# TWELITE_meas_2.net
KiCad netlist of a schematic drawn in EAGLE
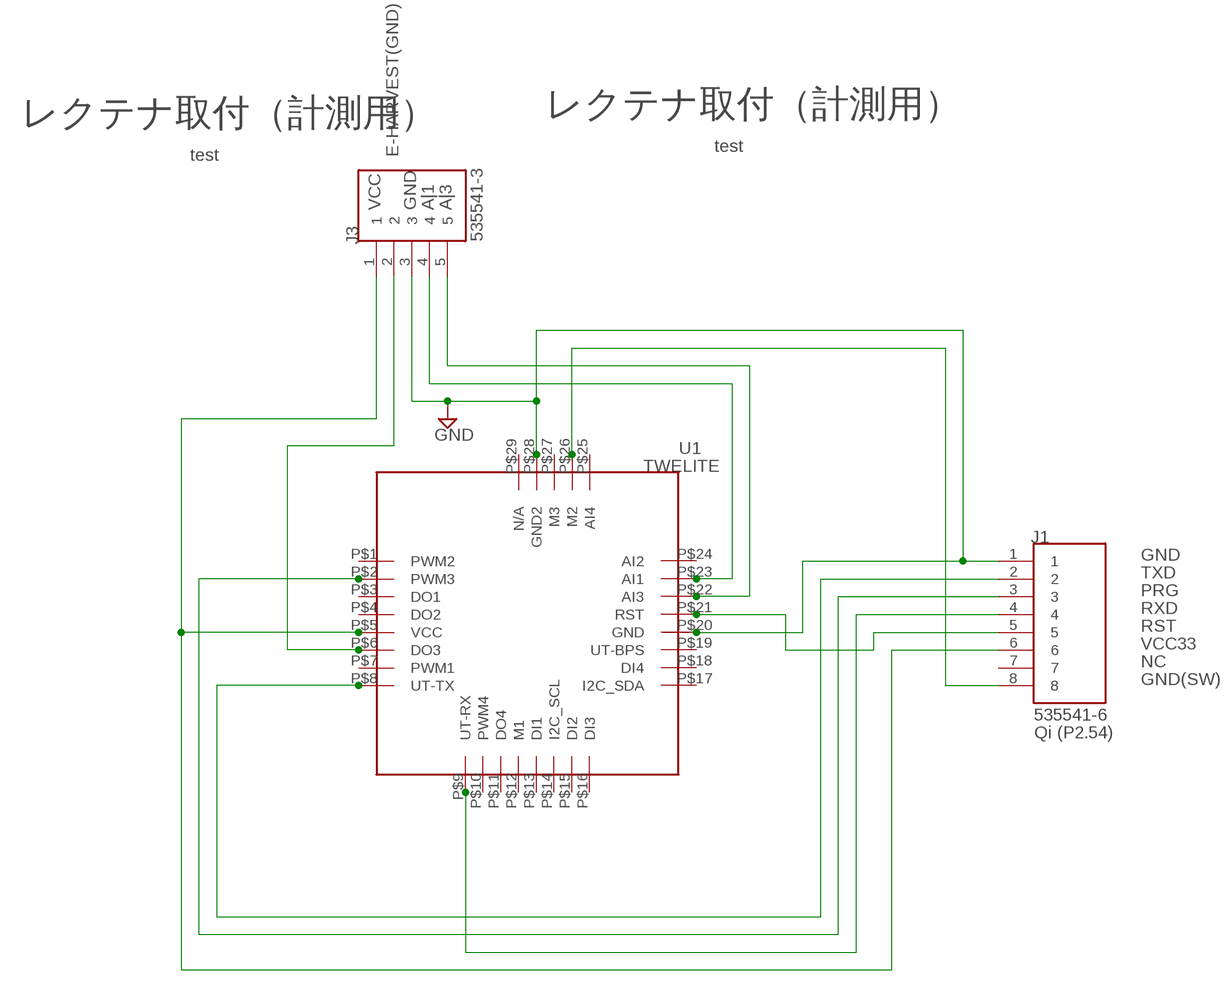
[diagram p0: schematic, sheet 1]

(export (version "E")
  (design (tool "Eeschema 10.0.6"))
  (components
    (comp (ref "J1")
      (value "535541-6")
      (footprint "eagle-import:TE_535541-6")
      (fields (field (name "MF") "TE Connectivity"))
      (libsource (lib "eagle-import") (part "535541-6"))
    )
    (comp (ref "J3")
      (value "535541-3")
      (footprint "eagle-import:TE_535541-3")
      (libsource (lib "eagle-import") (part "535541-3"))
    )
    (comp (ref "U1")
      (value "LITE_1")
      (footprint "eagle-import:LITE_1")
      (libsource (lib "eagle-import") (part "LITE_1"))
    )
  )
  (nets
    (net (code "1") (name "GND") (class "Default")
      (node (ref "J1") (pin "1") (pinfunction "1_1") (pintype "passive"))
      (node (ref "J3") (pin "3") (pinfunction "3_3") (pintype "passive"))
      (node (ref "U1") (pin "P$20") (pinfunction "GND_P$20") (pintype "bidirectional"))
      (node (ref "U1") (pin "P$28") (pinfunction "GND2_P$28") (pintype "bidirectional"))
    )
    (net (code "2") (name "Net-(U1-AI1)") (class "Default")
      (node (ref "J3") (pin "4") (pinfunction "4_4") (pintype "passive"))
      (node (ref "U1") (pin "P$23") (pinfunction "AI1_P$23") (pintype "bidirectional"))
    )
    (net (code "3") (name "Net-(U1-AI3)") (class "Default")
      (node (ref "J3") (pin "5") (pinfunction "5_5") (pintype "passive"))
      (node (ref "U1") (pin "P$22") (pinfunction "AI3_P$22") (pintype "bidirectional"))
    )
    (net (code "4") (name "Net-(U1-DO3)") (class "Default")
      (node (ref "J3") (pin "2") (pinfunction "2_2") (pintype "passive"))
      (node (ref "U1") (pin "P$6") (pinfunction "DO3_P$6") (pintype "bidirectional"))
    )
    (net (code "5") (name "Net-(U1-M2)") (class "Default")
      (node (ref "J1") (pin "8") (pinfunction "8_8") (pintype "passive"))
      (node (ref "U1") (pin "P$26") (pinfunction "M2_P$26") (pintype "bidirectional"))
    )
    (net (code "6") (name "Net-(U1-PWM3)") (class "Default")
      (node (ref "J1") (pin "3") (pinfunction "3_3") (pintype "passive"))
      (node (ref "U1") (pin "P$2") (pinfunction "PWM3_P$2") (pintype "bidirectional"))
    )
    (net (code "7") (name "Net-(U1-RST)") (class "Default")
      (node (ref "J1") (pin "5") (pinfunction "5_5") (pintype "passive"))
      (node (ref "U1") (pin "P$21") (pinfunction "RST_P$21") (pintype "bidirectional"))
    )
    (net (code "8") (name "Net-(U1-UT-RX)") (class "Default")
      (node (ref "J1") (pin "4") (pinfunction "4_4") (pintype "passive"))
      (node (ref "U1") (pin "P$9") (pinfunction "UT-RX_P$9") (pintype "bidirectional"))
    )
    (net (code "9") (name "Net-(U1-UT-TX)") (class "Default")
      (node (ref "J1") (pin "2") (pinfunction "2_2") (pintype "passive"))
      (node (ref "U1") (pin "P$8") (pinfunction "UT-TX_P$8") (pintype "bidirectional"))
    )
    (net (code "10") (name "Net-(U1-VCC)") (class "Default")
      (node (ref "J1") (pin "6") (pinfunction "6_6") (pintype "passive"))
      (node (ref "J3") (pin "1") (pinfunction "1_1") (pintype "passive"))
      (node (ref "U1") (pin "P$5") (pinfunction "VCC_P$5") (pintype "bidirectional"))
    )
    (net (code "11") (name "unconnected-(J1-Pad7)") (class "Default")
      (node (ref "J1") (pin "7") (pinfunction "7_7") (pintype "passive"))
    )
    (net (code "12") (name "unconnected-(U1-AI2-PadP$24)") (class "Default")
      (node (ref "U1") (pin "P$24") (pinfunction "AI2_P$24") (pintype "bidirectional"))
    )
    (net (code "13") (name "unconnected-(U1-AI4-PadP$25)") (class "Default")
      (node (ref "U1") (pin "P$25") (pinfunction "AI4_P$25") (pintype "bidirectional"))
    )
    (net (code "14") (name "unconnected-(U1-DI1-PadP$13)") (class "Default")
      (node (ref "U1") (pin "P$13") (pinfunction "DI1_P$13") (pintype "bidirectional"))
    )
    (net (code "15") (name "unconnected-(U1-DI2-PadP$15)") (class "Default")
      (node (ref "U1") (pin "P$15") (pinfunction "DI2_P$15") (pintype "bidirectional"))
    )
    (net (code "16") (name "unconnected-(U1-DI3-PadP$16)") (class "Default")
      (node (ref "U1") (pin "P$16") (pinfunction "DI3_P$16") (pintype "bidirectional"))
    )
    (net (code "17") (name "unconnected-(U1-DI4-PadP$18)") (class "Default")
      (node (ref "U1") (pin "P$18") (pinfunction "DI4_P$18") (pintype "bidirectional"))
    )
    (net (code "18") (name "unconnected-(U1-DO1-PadP$3)") (class "Default")
      (node (ref "U1") (pin "P$3") (pinfunction "DO1_P$3") (pintype "bidirectional"))
    )
    (net (code "19") (name "unconnected-(U1-DO2-PadP$4)") (class "Default")
      (node (ref "U1") (pin "P$4") (pinfunction "DO2_P$4") (pintype "bidirectional"))
    )
    (net (code "20") (name "unconnected-(U1-DO4-PadP$11)") (class "Default")
      (node (ref "U1") (pin "P$11") (pinfunction "DO4_P$11") (pintype "bidirectional"))
    )
    (net (code "21") (name "unconnected-(U1-I2C_SCL-PadP$14)") (class "Default")
      (node (ref "U1") (pin "P$14") (pinfunction "I2C_SCL_P$14") (pintype "bidirectional"))
    )
    (net (code "22") (name "unconnected-(U1-I2C_SDA-PadP$17)") (class "Default")
      (node (ref "U1") (pin "P$17") (pinfunction "I2C_SDA_P$17") (pintype "bidirectional"))
    )
    (net (code "23") (name "unconnected-(U1-M1-PadP$12)") (class "Default")
      (node (ref "U1") (pin "P$12") (pinfunction "M1_P$12") (pintype "bidirectional"))
    )
    (net (code "24") (name "unconnected-(U1-M3-PadP$27)") (class "Default")
      (node (ref "U1") (pin "P$27") (pinfunction "M3_P$27") (pintype "bidirectional"))
    )
    (net (code "25") (name "unconnected-(U1-N{slash}A-PadP$29)") (class "Default")
      (node (ref "U1") (pin "P$29") (pinfunction "N/A_P$29") (pintype "bidirectional"))
    )
    (net (code "26") (name "unconnected-(U1-PWM1-PadP$7)") (class "Default")
      (node (ref "U1") (pin "P$7") (pinfunction "PWM1_P$7") (pintype "bidirectional"))
    )
    (net (code "27") (name "unconnected-(U1-PWM2-PadP$1)") (class "Default")
      (node (ref "U1") (pin "P$1") (pinfunction "PWM2_P$1") (pintype "bidirectional"))
    )
    (net (code "28") (name "unconnected-(U1-PWM4-PadP$10)") (class "Default")
      (node (ref "U1") (pin "P$10") (pinfunction "PWM4_P$10") (pintype "bidirectional"))
    )
    (net (code "29") (name "unconnected-(U1-UT-BPS-PadP$19)") (class "Default")
      (node (ref "U1") (pin "P$19") (pinfunction "UT-BPS_P$19") (pintype "bidirectional"))
    )
  )
)
